# LANModule.net
KiCad netlist of a schematic drawn in Altium Designer
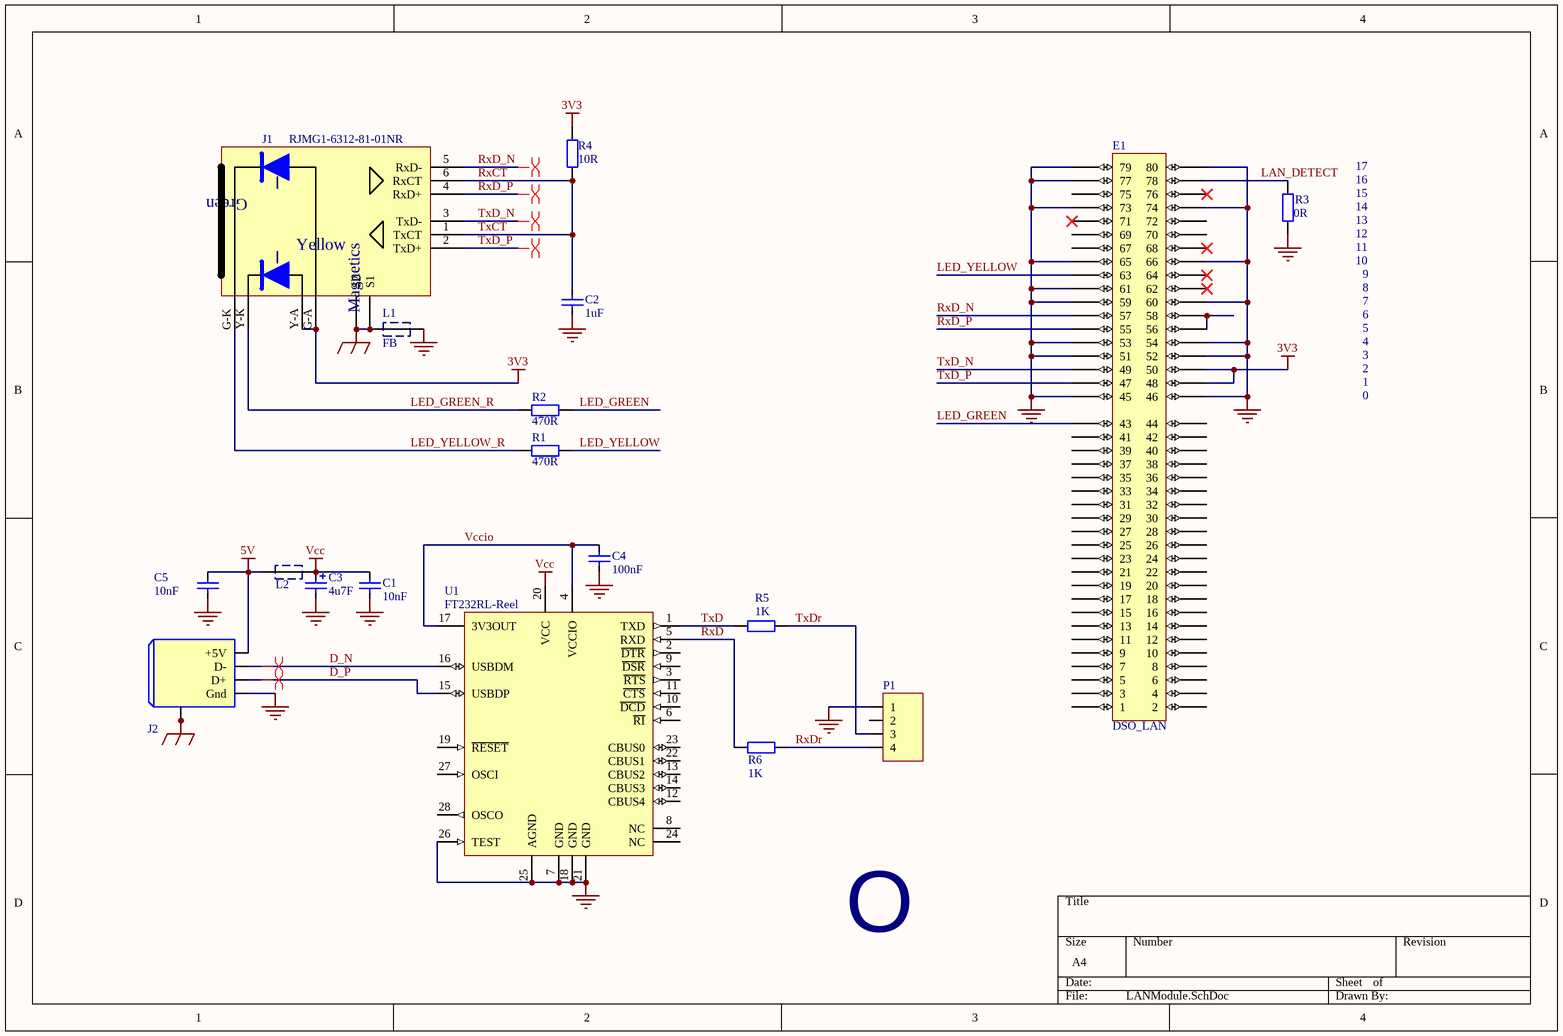
[diagram p0: LANModule.SchDoc]

(export (version "E")
  (design (tool "Eeschema 10.0.6"))
  (components
    (comp (ref "C1")
      (value "10nF")
      (footprint "CCNP2012-0805")
      (description "Capacitor")
      (fields
        (field (name "MANUFACTURER") "Generic Components")
        (field (name "PUBLISHER") "Altium Hobart Technology Centre")
      )
      (libsource (lib "MyLibrary") (part "Cap"))
    )
    (comp (ref "C2")
      (value "1uF")
      (footprint "CCNP2012-0805")
      (description "Capacitor")
      (fields
        (field (name "MANUFACTURER") "Generic Components")
        (field (name "PUBLISHER") "Altium Hobart Technology Centre")
      )
      (libsource (lib "MyLibrary") (part "Cap"))
    )
    (comp (ref "C3")
      (value "4u7F")
      (footprint "CC2012-0805")
      (description "Polarized Capacitor")
      (fields
        (field (name "MANUFACTURER") "Generic Components")
        (field (name "PUBLISHER") "Altium Hobart Technology Centre")
      )
      (libsource (lib "MyLibrary") (part "Cap Polar"))
    )
    (comp (ref "C4")
      (value "100nF")
      (footprint "CCNP2012-0805")
      (description "Capacitor")
      (fields
        (field (name "MANUFACTURER") "Generic Components")
        (field (name "PUBLISHER") "Altium Hobart Technology Centre")
      )
      (libsource (lib "MyLibrary") (part "Cap"))
    )
    (comp (ref "C5")
      (value "10nF")
      (footprint "CCNP2012-0805")
      (description "Capacitor")
      (fields
        (field (name "MANUFACTURER") "Generic Components")
        (field (name "PUBLISHER") "Altium Hobart Technology Centre")
      )
      (libsource (lib "MyLibrary") (part "Cap"))
    )
    (comp (ref "E1") (value "DSO_LAN") (footprint "DSO_LAN") (libsource (lib "MyLibrary") (part "DSO_LAN")))
    (comp (ref "J1")
      (value "RJMG1-6312-81-01NR")
      (footprint "MagJack - Amphenol RJMG16")
      (description "RJ45 Jack with Magnetics (Amphenol)")
      (libsource (lib "MySchLib") (part "MagJack-RJMG1-6312-81-01NR"))
    )
    (comp (ref "J2")
      (value "USB Type A Plug")
      (footprint "USB_BCon")
      (description "MOLEX 48037-1000")
      (libsource (lib "MyLibrary") (part "USB_TYPE_A_PLUG"))
    )
    (comp (ref "L1")
      (value "FB")
      (footprint "CR2012-0805")
      (description "Ferrite Bead (0805) 0.045OHM, 2A")
      (libsource (lib "MyLibrary") (part "Ferrite Bead 0805"))
    )
    (comp (ref "L2")
      (value "Ferrite Bead")
      (footprint "FB2012-0805")
      (description "Ferrite Bead SMT 0805, TDK MPZ2012S102AT, 0.15OHM, 1.5A")
      (libsource (lib "MyLibrary") (part "Ferrite Bead 0805"))
    )
    (comp (ref "Logo")
      (value "OSHW Logo")
      (footprint "OSHW")
      (libsource (lib "MyLibrary") (part "OSHW Logo"))
    )
    (comp (ref "P1")
      (value "Header 1x4H")
      (footprint "HDR1X4H")
      (description "Header, 4-Pin, Right Angle")
      (fields (field (name "PUBLISHER") "Altium Limited"))
      (libsource (lib "MyLibrary") (part "Header 1x4H"))
    )
    (comp (ref "R1")
      (value "470R")
      (footprint "CR2012-0805")
      (description "Resistor")
      (fields
        (field (name "MANUFACTURER") "Generic Components")
        (field (name "PUBLISHER") "Altium Hobart Technology Centre")
      )
      (libsource (lib "MyLibrary") (part "Res_CR0805"))
    )
    (comp (ref "R2")
      (value "470R")
      (footprint "CR2012-0805")
      (description "Resistor")
      (fields
        (field (name "MANUFACTURER") "Generic Components")
        (field (name "PUBLISHER") "Altium Hobart Technology Centre")
      )
      (libsource (lib "MyLibrary") (part "Res_CR0805"))
    )
    (comp (ref "R3")
      (value "0R")
      (footprint "CR2012-0805")
      (description "Resistor")
      (fields
        (field (name "MANUFACTURER") "Generic Components")
        (field (name "PUBLISHER") "Altium Hobart Technology Centre")
      )
      (libsource (lib "") (part "Res_CR0805_1"))
    )
    (comp (ref "R4")
      (value "10R")
      (footprint "CR2012-0805")
      (description "Resistor")
      (fields
        (field (name "MANUFACTURER") "Generic Components")
        (field (name "PUBLISHER") "Altium Hobart Technology Centre")
      )
      (libsource (lib "") (part "Res_CR0805_2"))
    )
    (comp (ref "R5")
      (value "1K")
      (footprint "CR2012-0805")
      (description "Resistor")
      (fields
        (field (name "MANUFACTURER") "Generic Components")
        (field (name "PUBLISHER") "Altium Hobart Technology Centre")
      )
      (libsource (lib "MyLibrary") (part "Res"))
    )
    (comp (ref "R6")
      (value "1K")
      (footprint "CR2012-0805")
      (description "Resistor")
      (fields
        (field (name "MANUFACTURER") "Generic Components")
        (field (name "PUBLISHER") "Altium Hobart Technology Centre")
      )
      (libsource (lib "MyLibrary") (part "Res"))
    )
    (comp (ref "U1")
      (value "FT232RL-Reel")
      (footprint "SSOP-28_N")
      (description "USB UART Asynchronous Serial Data Transfer Chip, SSOP-28, Tape and Reel")
      (fields (field (name "PUBLISHER") "Altium Limited"))
      (libsource (lib "FTDI Communication UART") (part "FT232RL-Reel"))
    )
  )
  (nets
    (net (code "1") (name "/D_N") (class "Default")
      (node (ref "J2") (pin "D-") (pinfunction "D-_D-") (pintype "passive"))
      (node (ref "U1") (pin "16") (pinfunction "USBDM_16") (pintype "bidirectional"))
    )
    (net (code "2") (name "/D_P") (class "Default")
      (node (ref "J2") (pin "D+") (pinfunction "D+_D+") (pintype "passive"))
      (node (ref "U1") (pin "15") (pinfunction "USBDP_15") (pintype "bidirectional"))
    )
    (net (code "3") (name "/LAN_DETECT") (class "Default")
      (node (ref "E1") (pin "78") (pinfunction "78_78") (pintype "bidirectional"))
      (node (ref "R3") (pin "1") (pinfunction "1_1") (pintype "passive"))
    )
    (net (code "4") (name "/LED_GREEN") (class "Default")
      (node (ref "E1") (pin "43") (pinfunction "43_43") (pintype "bidirectional"))
      (node (ref "R2") (pin "2") (pinfunction "2_2") (pintype "passive"))
    )
    (net (code "5") (name "/LED_GREEN_R") (class "Default")
      (node (ref "J1") (pin "Y-K") (pinfunction "Y-K_Y-K") (pintype "passive"))
      (node (ref "R2") (pin "1") (pinfunction "1_1") (pintype "passive"))
    )
    (net (code "6") (name "/LED_YELLOW") (class "Default")
      (node (ref "E1") (pin "63") (pinfunction "63_63") (pintype "bidirectional"))
      (node (ref "R1") (pin "2") (pinfunction "2_2") (pintype "passive"))
    )
    (net (code "7") (name "/LED_YELLOW_R") (class "Default")
      (node (ref "J1") (pin "G-K") (pinfunction "G-K_G-K") (pintype "passive"))
      (node (ref "R1") (pin "1") (pinfunction "1_1") (pintype "passive"))
    )
    (net (code "8") (name "/RxCT") (class "Default")
      (node (ref "C2") (pin "2") (pinfunction "2_2") (pintype "passive"))
      (node (ref "J1") (pin "1") (pinfunction "TxCT_1") (pintype "passive"))
      (node (ref "J1") (pin "6") (pinfunction "RxCT_6") (pintype "passive"))
      (node (ref "R4") (pin "1") (pinfunction "1_1") (pintype "passive"))
    )
    (net (code "9") (name "/RxD") (class "Default")
      (node (ref "R6") (pin "1") (pinfunction "1_1") (pintype "passive"))
      (node (ref "U1") (pin "5") (pinfunction "RXD_5") (pintype "input"))
    )
    (net (code "10") (name "/RxD_N") (class "Default")
      (node (ref "E1") (pin "57") (pinfunction "57_57") (pintype "bidirectional"))
      (node (ref "J1") (pin "5") (pinfunction "RxD-_5") (pintype "passive"))
    )
    (net (code "11") (name "/RxD_P") (class "Default")
      (node (ref "E1") (pin "55") (pinfunction "55_55") (pintype "bidirectional"))
      (node (ref "J1") (pin "4") (pinfunction "RxD+_4") (pintype "passive"))
    )
    (net (code "12") (name "/RxDr") (class "Default")
      (node (ref "P1") (pin "4") (pinfunction "4_4") (pintype "passive"))
      (node (ref "R6") (pin "2") (pinfunction "2_2") (pintype "passive"))
    )
    (net (code "13") (name "/TxD") (class "Default")
      (node (ref "R5") (pin "1") (pinfunction "1_1") (pintype "passive"))
      (node (ref "U1") (pin "1") (pinfunction "TXD_1") (pintype "output"))
    )
    (net (code "14") (name "/TxD_N") (class "Default")
      (node (ref "E1") (pin "49") (pinfunction "49_49") (pintype "bidirectional"))
      (node (ref "J1") (pin "3") (pinfunction "TxD-_3") (pintype "passive"))
    )
    (net (code "15") (name "/TxD_P") (class "Default")
      (node (ref "E1") (pin "47") (pinfunction "47_47") (pintype "bidirectional"))
      (node (ref "J1") (pin "2") (pinfunction "TxD+_2") (pintype "passive"))
    )
    (net (code "16") (name "/TxDr") (class "Default")
      (node (ref "P1") (pin "3") (pinfunction "3_3") (pintype "passive"))
      (node (ref "R5") (pin "2") (pinfunction "2_2") (pintype "passive"))
    )
    (net (code "17") (name "/Vccio") (class "Default")
      (node (ref "C4") (pin "2") (pinfunction "2_2") (pintype "passive"))
      (node (ref "U1") (pin "17") (pinfunction "3V3OUT_17") (pintype "power_in"))
      (node (ref "U1") (pin "4") (pinfunction "VCCIO_4") (pintype "power_in"))
    )
    (net (code "18") (name "3V3") (class "Default")
      (node (ref "E1") (pin "48") (pinfunction "48_48") (pintype "bidirectional"))
      (node (ref "E1") (pin "50") (pinfunction "50_50") (pintype "bidirectional"))
      (node (ref "J1") (pin "G-A") (pinfunction "G-A_G-A") (pintype "passive"))
      (node (ref "J1") (pin "Y-A") (pinfunction "Y-A_Y-A") (pintype "passive"))
      (node (ref "R4") (pin "2") (pinfunction "2_2") (pintype "passive"))
    )
    (net (code "19") (name "5V") (class "Default")
      (node (ref "C5") (pin "2") (pinfunction "2_2") (pintype "passive"))
      (node (ref "J2") (pin "5V") (pinfunction "+5V_5V") (pintype "power_in"))
      (node (ref "L2") (pin "1") (pinfunction "1_1") (pintype "passive"))
    )
    (net (code "20") (name "EARTH") (class "Default")
      (node (ref "J1") (pin "S1") (pinfunction "S1_S1") (pintype "passive"))
      (node (ref "J1") (pin "S2") (pinfunction "S2_S2") (pintype "passive"))
      (node (ref "J2") (pin "Shield1") (pinfunction "USBShd_Shield1") (pintype "passive"))
      (node (ref "J2") (pin "Shield2") (pinfunction "USBShd_Shield2") (pintype "passive"))
      (node (ref "L1") (pin "1") (pinfunction "1_1") (pintype "passive"))
    )
    (net (code "21") (name "GND") (class "Default")
      (node (ref "C1") (pin "1") (pinfunction "1_1") (pintype "passive"))
      (node (ref "C2") (pin "1") (pinfunction "1_1") (pintype "passive"))
      (node (ref "C3") (pin "2") (pinfunction "2_2") (pintype "passive"))
      (node (ref "C4") (pin "1") (pinfunction "1_1") (pintype "passive"))
      (node (ref "C5") (pin "1") (pinfunction "1_1") (pintype "passive"))
      (node (ref "E1") (pin "45") (pinfunction "45_45") (pintype "bidirectional"))
      (node (ref "E1") (pin "46") (pinfunction "46_46") (pintype "bidirectional"))
      (node (ref "E1") (pin "51") (pinfunction "51_51") (pintype "bidirectional"))
      (node (ref "E1") (pin "52") (pinfunction "52_52") (pintype "bidirectional"))
      (node (ref "E1") (pin "53") (pinfunction "53_53") (pintype "bidirectional"))
      (node (ref "E1") (pin "54") (pinfunction "54_54") (pintype "bidirectional"))
      (node (ref "E1") (pin "59") (pinfunction "59_59") (pintype "bidirectional"))
      (node (ref "E1") (pin "60") (pinfunction "60_60") (pintype "bidirectional"))
      (node (ref "E1") (pin "61") (pinfunction "61_61") (pintype "bidirectional"))
      (node (ref "E1") (pin "65") (pinfunction "65_65") (pintype "bidirectional"))
      (node (ref "E1") (pin "66") (pinfunction "66_66") (pintype "bidirectional"))
      (node (ref "E1") (pin "73") (pinfunction "73_73") (pintype "bidirectional"))
      (node (ref "E1") (pin "74") (pinfunction "74_74") (pintype "bidirectional"))
      (node (ref "E1") (pin "77") (pinfunction "77_77") (pintype "bidirectional"))
      (node (ref "E1") (pin "79") (pinfunction "79_79") (pintype "bidirectional"))
      (node (ref "E1") (pin "80") (pinfunction "80_80") (pintype "bidirectional"))
      (node (ref "J2") (pin "Gnd") (pinfunction "Gnd_Gnd") (pintype "passive"))
      (node (ref "L1") (pin "2") (pinfunction "2_2") (pintype "passive"))
      (node (ref "P1") (pin "1") (pinfunction "1_1") (pintype "passive"))
      (node (ref "R3") (pin "2") (pinfunction "2_2") (pintype "passive"))
      (node (ref "U1") (pin "18") (pinfunction "GND_18") (pintype "power_in"))
      (node (ref "U1") (pin "21") (pinfunction "GND_21") (pintype "power_in"))
      (node (ref "U1") (pin "25") (pinfunction "AGND_25") (pintype "power_in"))
      (node (ref "U1") (pin "26") (pinfunction "TEST_26") (pintype "input"))
      (node (ref "U1") (pin "7") (pinfunction "GND_7") (pintype "power_in"))
    )
    (net (code "22") (name "Net-(E1-Pad56)") (class "Default")
      (node (ref "E1") (pin "56") (pinfunction "56_56") (pintype "bidirectional"))
      (node (ref "E1") (pin "58") (pinfunction "58_58") (pintype "bidirectional"))
    )
    (net (code "23") (name "Vcc") (class "Default")
      (node (ref "C1") (pin "2") (pinfunction "2_2") (pintype "passive"))
      (node (ref "C3") (pin "1") (pinfunction "1_1") (pintype "passive"))
      (node (ref "L2") (pin "2") (pinfunction "2_2") (pintype "passive"))
      (node (ref "U1") (pin "20") (pinfunction "VCC_20") (pintype "power_in"))
    )
    (net (code "24") (name "unconnected-(E1-Pad1)") (class "Default")
      (node (ref "E1") (pin "1") (pinfunction "1_1") (pintype "bidirectional"))
    )
    (net (code "25") (name "unconnected-(E1-Pad2)") (class "Default")
      (node (ref "E1") (pin "2") (pinfunction "2_2") (pintype "bidirectional"))
    )
    (net (code "26") (name "unconnected-(E1-Pad3)") (class "Default")
      (node (ref "E1") (pin "3") (pinfunction "3_3") (pintype "bidirectional"))
    )
    (net (code "27") (name "unconnected-(E1-Pad4)") (class "Default")
      (node (ref "E1") (pin "4") (pinfunction "4_4") (pintype "bidirectional"))
    )
    (net (code "28") (name "unconnected-(E1-Pad5)") (class "Default")
      (node (ref "E1") (pin "5") (pinfunction "5_5") (pintype "bidirectional"))
    )
    (net (code "29") (name "unconnected-(E1-Pad6)") (class "Default")
      (node (ref "E1") (pin "6") (pinfunction "6_6") (pintype "bidirectional"))
    )
    (net (code "30") (name "unconnected-(E1-Pad7)") (class "Default")
      (node (ref "E1") (pin "7") (pinfunction "7_7") (pintype "bidirectional"))
    )
    (net (code "31") (name "unconnected-(E1-Pad8)") (class "Default")
      (node (ref "E1") (pin "8") (pinfunction "8_8") (pintype "bidirectional"))
    )
    (net (code "32") (name "unconnected-(E1-Pad9)") (class "Default")
      (node (ref "E1") (pin "9") (pinfunction "9_9") (pintype "bidirectional"))
    )
    (net (code "33") (name "unconnected-(E1-Pad10)") (class "Default")
      (node (ref "E1") (pin "10") (pinfunction "10_10") (pintype "bidirectional"))
    )
    (net (code "34") (name "unconnected-(E1-Pad11)") (class "Default")
      (node (ref "E1") (pin "11") (pinfunction "11_11") (pintype "bidirectional"))
    )
    (net (code "35") (name "unconnected-(E1-Pad12)") (class "Default")
      (node (ref "E1") (pin "12") (pinfunction "12_12") (pintype "bidirectional"))
    )
    (net (code "36") (name "unconnected-(E1-Pad13)") (class "Default")
      (node (ref "E1") (pin "13") (pinfunction "13_13") (pintype "bidirectional"))
    )
    (net (code "37") (name "unconnected-(E1-Pad14)") (class "Default")
      (node (ref "E1") (pin "14") (pinfunction "14_14") (pintype "bidirectional"))
    )
    (net (code "38") (name "unconnected-(E1-Pad15)") (class "Default")
      (node (ref "E1") (pin "15") (pinfunction "15_15") (pintype "bidirectional"))
    )
    (net (code "39") (name "unconnected-(E1-Pad16)") (class "Default")
      (node (ref "E1") (pin "16") (pinfunction "16_16") (pintype "bidirectional"))
    )
    (net (code "40") (name "unconnected-(E1-Pad17)") (class "Default")
      (node (ref "E1") (pin "17") (pinfunction "17_17") (pintype "bidirectional"))
    )
    (net (code "41") (name "unconnected-(E1-Pad18)") (class "Default")
      (node (ref "E1") (pin "18") (pinfunction "18_18") (pintype "bidirectional"))
    )
    (net (code "42") (name "unconnected-(E1-Pad19)") (class "Default")
      (node (ref "E1") (pin "19") (pinfunction "19_19") (pintype "bidirectional"))
    )
    (net (code "43") (name "unconnected-(E1-Pad20)") (class "Default")
      (node (ref "E1") (pin "20") (pinfunction "20_20") (pintype "bidirectional"))
    )
    (net (code "44") (name "unconnected-(E1-Pad21)") (class "Default")
      (node (ref "E1") (pin "21") (pinfunction "21_21") (pintype "bidirectional"))
    )
    (net (code "45") (name "unconnected-(E1-Pad22)") (class "Default")
      (node (ref "E1") (pin "22") (pinfunction "22_22") (pintype "bidirectional"))
    )
    (net (code "46") (name "unconnected-(E1-Pad23)") (class "Default")
      (node (ref "E1") (pin "23") (pinfunction "23_23") (pintype "bidirectional"))
    )
    (net (code "47") (name "unconnected-(E1-Pad24)") (class "Default")
      (node (ref "E1") (pin "24") (pinfunction "24_24") (pintype "bidirectional"))
    )
    (net (code "48") (name "unconnected-(E1-Pad25)") (class "Default")
      (node (ref "E1") (pin "25") (pinfunction "25_25") (pintype "bidirectional"))
    )
    (net (code "49") (name "unconnected-(E1-Pad26)") (class "Default")
      (node (ref "E1") (pin "26") (pinfunction "26_26") (pintype "bidirectional"))
    )
    (net (code "50") (name "unconnected-(E1-Pad27)") (class "Default")
      (node (ref "E1") (pin "27") (pinfunction "27_27") (pintype "bidirectional"))
    )
    (net (code "51") (name "unconnected-(E1-Pad28)") (class "Default")
      (node (ref "E1") (pin "28") (pinfunction "28_28") (pintype "bidirectional"))
    )
    (net (code "52") (name "unconnected-(E1-Pad29)") (class "Default")
      (node (ref "E1") (pin "29") (pinfunction "29_29") (pintype "bidirectional"))
    )
    (net (code "53") (name "unconnected-(E1-Pad30)") (class "Default")
      (node (ref "E1") (pin "30") (pinfunction "30_30") (pintype "bidirectional"))
    )
    (net (code "54") (name "unconnected-(E1-Pad31)") (class "Default")
      (node (ref "E1") (pin "31") (pinfunction "31_31") (pintype "bidirectional"))
    )
    (net (code "55") (name "unconnected-(E1-Pad32)") (class "Default")
      (node (ref "E1") (pin "32") (pinfunction "32_32") (pintype "bidirectional"))
    )
    (net (code "56") (name "unconnected-(E1-Pad33)") (class "Default")
      (node (ref "E1") (pin "33") (pinfunction "33_33") (pintype "bidirectional"))
    )
    (net (code "57") (name "unconnected-(E1-Pad34)") (class "Default")
      (node (ref "E1") (pin "34") (pinfunction "34_34") (pintype "bidirectional"))
    )
    (net (code "58") (name "unconnected-(E1-Pad35)") (class "Default")
      (node (ref "E1") (pin "35") (pinfunction "35_35") (pintype "bidirectional"))
    )
    (net (code "59") (name "unconnected-(E1-Pad36)") (class "Default")
      (node (ref "E1") (pin "36") (pinfunction "36_36") (pintype "bidirectional"))
    )
    (net (code "60") (name "unconnected-(E1-Pad37)") (class "Default")
      (node (ref "E1") (pin "37") (pinfunction "37_37") (pintype "bidirectional"))
    )
    (net (code "61") (name "unconnected-(E1-Pad38)") (class "Default")
      (node (ref "E1") (pin "38") (pinfunction "38_38") (pintype "bidirectional"))
    )
    (net (code "62") (name "unconnected-(E1-Pad39)") (class "Default")
      (node (ref "E1") (pin "39") (pinfunction "39_39") (pintype "bidirectional"))
    )
    (net (code "63") (name "unconnected-(E1-Pad40)") (class "Default")
      (node (ref "E1") (pin "40") (pinfunction "40_40") (pintype "bidirectional"))
    )
    (net (code "64") (name "unconnected-(E1-Pad41)") (class "Default")
      (node (ref "E1") (pin "41") (pinfunction "41_41") (pintype "bidirectional"))
    )
    (net (code "65") (name "unconnected-(E1-Pad42)") (class "Default")
      (node (ref "E1") (pin "42") (pinfunction "42_42") (pintype "bidirectional"))
    )
    (net (code "66") (name "unconnected-(E1-Pad44)") (class "Default")
      (node (ref "E1") (pin "44") (pinfunction "44_44") (pintype "bidirectional"))
    )
    (net (code "67") (name "unconnected-(E1-Pad62)") (class "Default")
      (node (ref "E1") (pin "62") (pinfunction "62_62") (pintype "bidirectional+no_connect"))
    )
    (net (code "68") (name "unconnected-(E1-Pad64)") (class "Default")
      (node (ref "E1") (pin "64") (pinfunction "64_64") (pintype "bidirectional+no_connect"))
    )
    (net (code "69") (name "unconnected-(E1-Pad67)") (class "Default")
      (node (ref "E1") (pin "67") (pinfunction "67_67") (pintype "bidirectional"))
    )
    (net (code "70") (name "unconnected-(E1-Pad68)") (class "Default")
      (node (ref "E1") (pin "68") (pinfunction "68_68") (pintype "bidirectional+no_connect"))
    )
    (net (code "71") (name "unconnected-(E1-Pad69)") (class "Default")
      (node (ref "E1") (pin "69") (pinfunction "69_69") (pintype "bidirectional"))
    )
    (net (code "72") (name "unconnected-(E1-Pad70)") (class "Default")
      (node (ref "E1") (pin "70") (pinfunction "70_70") (pintype "bidirectional"))
    )
    (net (code "73") (name "unconnected-(E1-Pad71)") (class "Default")
      (node (ref "E1") (pin "71") (pinfunction "71_71") (pintype "bidirectional+no_connect"))
    )
    (net (code "74") (name "unconnected-(E1-Pad72)") (class "Default")
      (node (ref "E1") (pin "72") (pinfunction "72_72") (pintype "bidirectional"))
    )
    (net (code "75") (name "unconnected-(E1-Pad75)") (class "Default")
      (node (ref "E1") (pin "75") (pinfunction "75_75") (pintype "bidirectional"))
    )
    (net (code "76") (name "unconnected-(E1-Pad76)") (class "Default")
      (node (ref "E1") (pin "76") (pinfunction "76_76") (pintype "bidirectional+no_connect"))
    )
    (net (code "77") (name "unconnected-(P1-Pad2)") (class "Default")
      (node (ref "P1") (pin "2") (pinfunction "2_2") (pintype "passive"))
    )
    (net (code "78") (name "unconnected-(U1-CBUS0-Pad23)") (class "Default")
      (node (ref "U1") (pin "23") (pinfunction "CBUS0_23") (pintype "bidirectional"))
    )
    (net (code "79") (name "unconnected-(U1-CBUS1-Pad22)") (class "Default")
      (node (ref "U1") (pin "22") (pinfunction "CBUS1_22") (pintype "bidirectional"))
    )
    (net (code "80") (name "unconnected-(U1-CBUS2-Pad13)") (class "Default")
      (node (ref "U1") (pin "13") (pinfunction "CBUS2_13") (pintype "bidirectional"))
    )
    (net (code "81") (name "unconnected-(U1-CBUS3-Pad14)") (class "Default")
      (node (ref "U1") (pin "14") (pinfunction "CBUS3_14") (pintype "bidirectional"))
    )
    (net (code "82") (name "unconnected-(U1-CBUS4-Pad12)") (class "Default")
      (node (ref "U1") (pin "12") (pinfunction "CBUS4_12") (pintype "bidirectional"))
    )
    (net (code "83") (name "unconnected-(U1-NC-Pad8)") (class "Default")
      (node (ref "U1") (pin "8") (pinfunction "NC_8") (pintype "passive"))
    )
    (net (code "84") (name "unconnected-(U1-NC-Pad24)") (class "Default")
      (node (ref "U1") (pin "24") (pinfunction "NC_24") (pintype "passive"))
    )
    (net (code "85") (name "unconnected-(U1-OSCI-Pad27)") (class "Default")
      (node (ref "U1") (pin "27") (pinfunction "OSCI_27") (pintype "input"))
    )
    (net (code "86") (name "unconnected-(U1-OSCO-Pad28)") (class "Default")
      (node (ref "U1") (pin "28") (pinfunction "OSCO_28") (pintype "output"))
    )
    (net (code "87") (name "unconnected-(U1-~{CTS}-Pad11)") (class "Default")
      (node (ref "U1") (pin "11") (pinfunction "~{CTS}_11") (pintype "input"))
    )
    (net (code "88") (name "unconnected-(U1-~{DCD}-Pad10)") (class "Default")
      (node (ref "U1") (pin "10") (pinfunction "~{DCD}_10") (pintype "input"))
    )
    (net (code "89") (name "unconnected-(U1-~{DSR}-Pad9)") (class "Default")
      (node (ref "U1") (pin "9") (pinfunction "~{DSR}_9") (pintype "input"))
    )
    (net (code "90") (name "unconnected-(U1-~{DTR}-Pad2)") (class "Default")
      (node (ref "U1") (pin "2") (pinfunction "~{DTR}_2") (pintype "output"))
    )
    (net (code "91") (name "unconnected-(U1-~{RESET}-Pad19)") (class "Default")
      (node (ref "U1") (pin "19") (pinfunction "~{RESET}_19") (pintype "input"))
    )
    (net (code "92") (name "unconnected-(U1-~{RI}-Pad6)") (class "Default")
      (node (ref "U1") (pin "6") (pinfunction "~{RI}_6") (pintype "input"))
    )
    (net (code "93") (name "unconnected-(U1-~{RTS}-Pad3)") (class "Default")
      (node (ref "U1") (pin "3") (pinfunction "~{RTS}_3") (pintype "output"))
    )
  )
)
